# Joystick.net
KiCad netlist of a schematic drawn in EAGLE
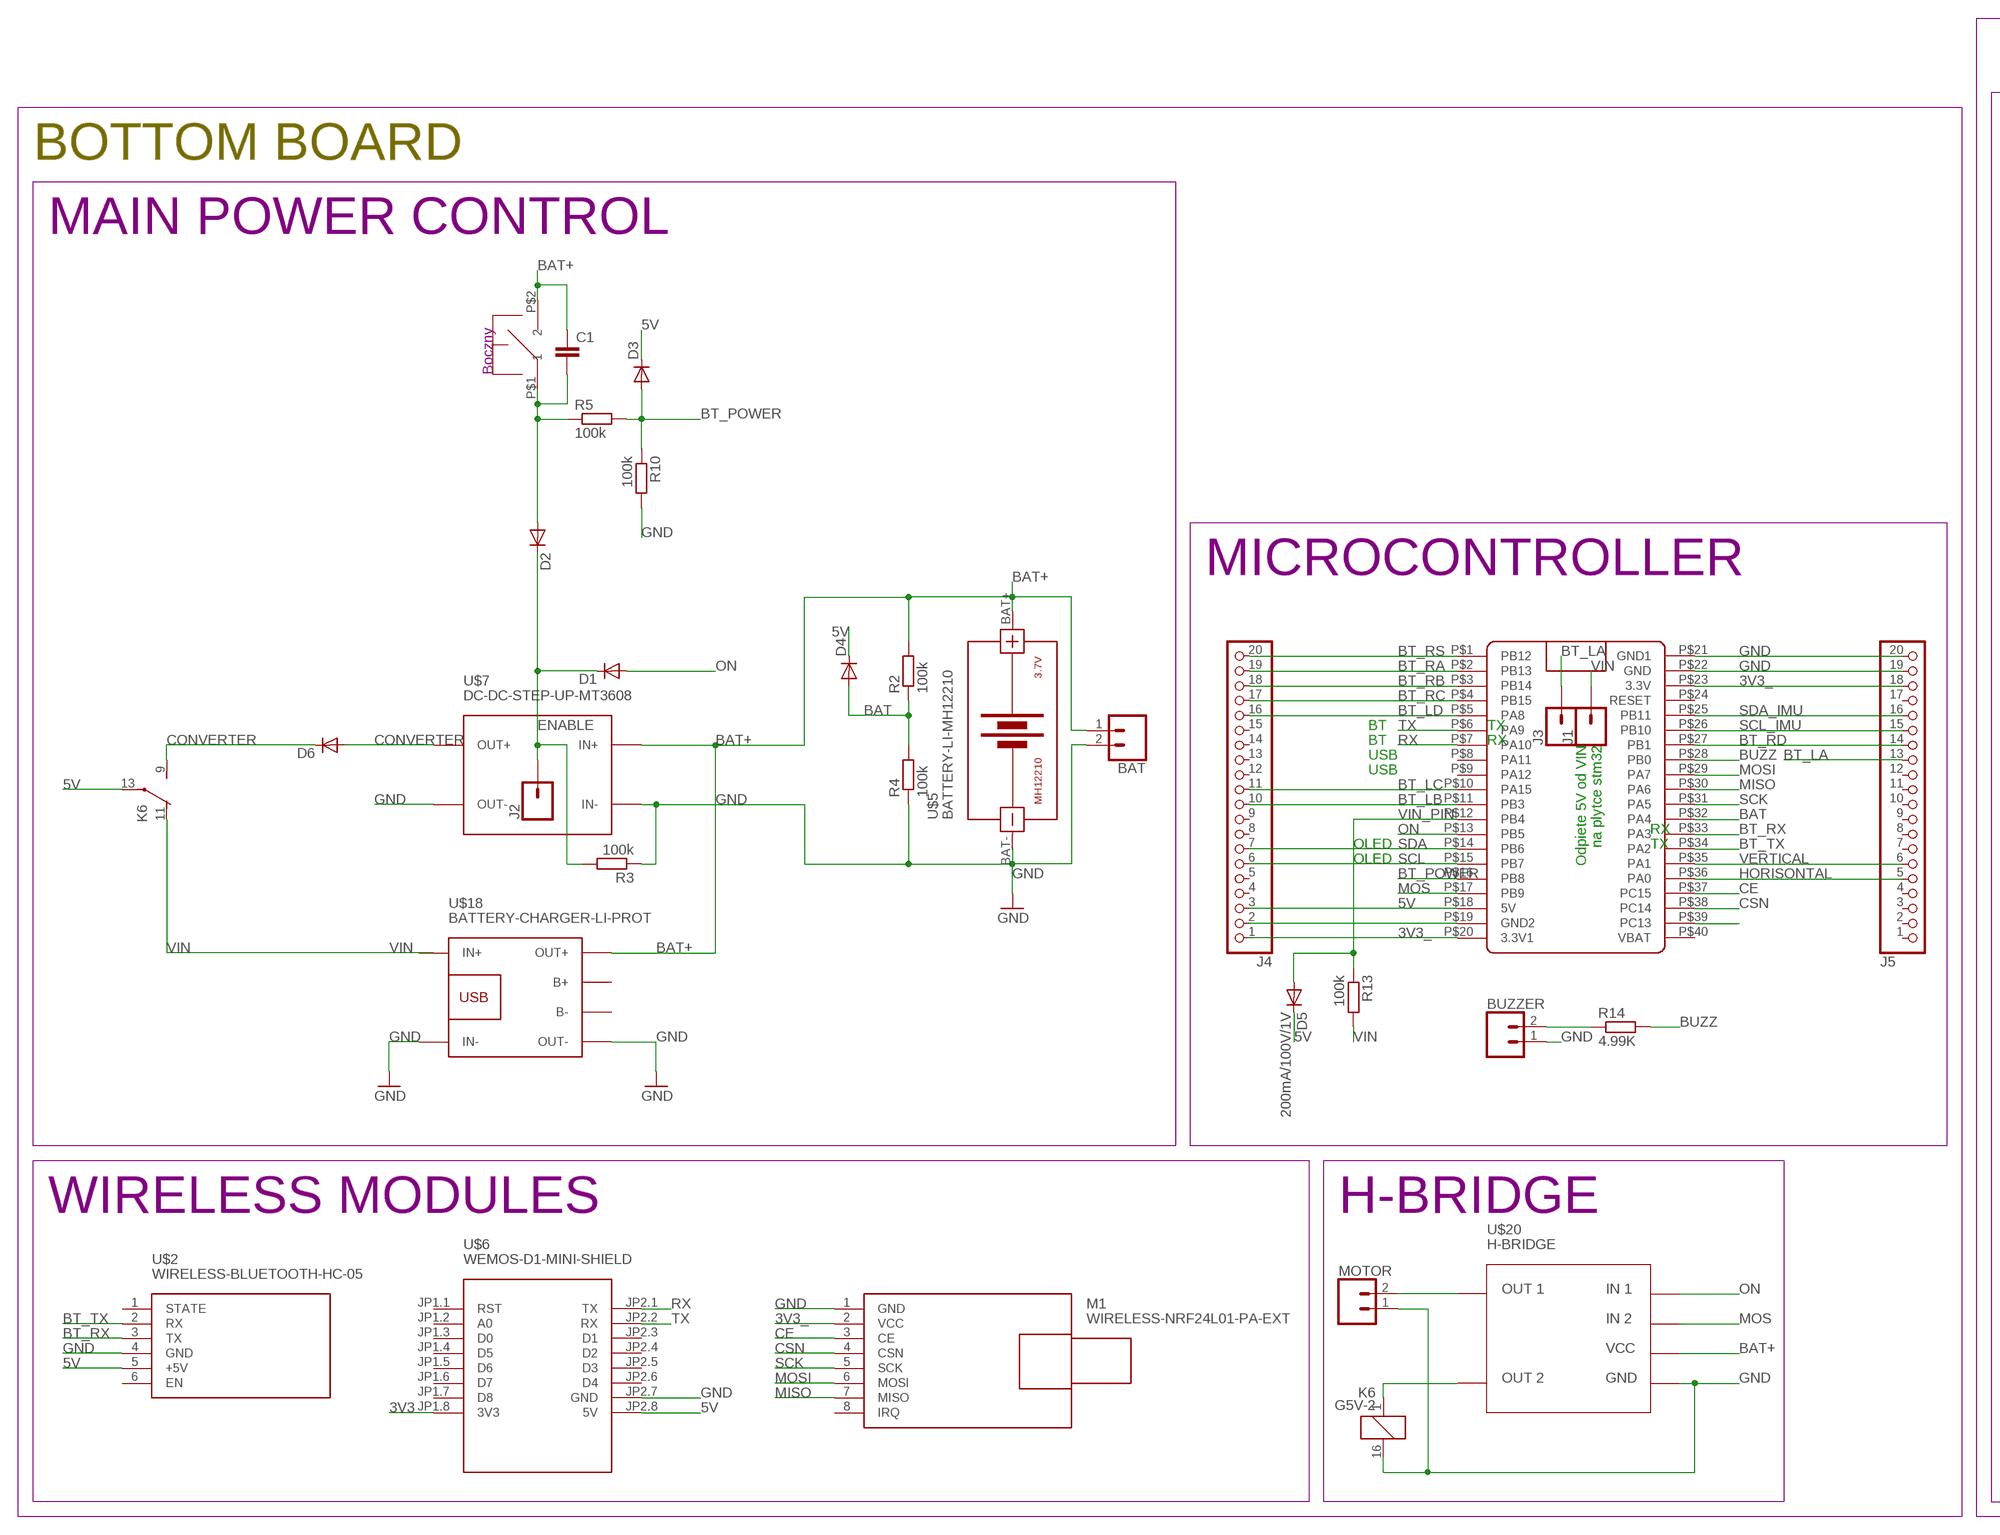
[diagram p0: schematic, sheet 1, part 1 of 2]
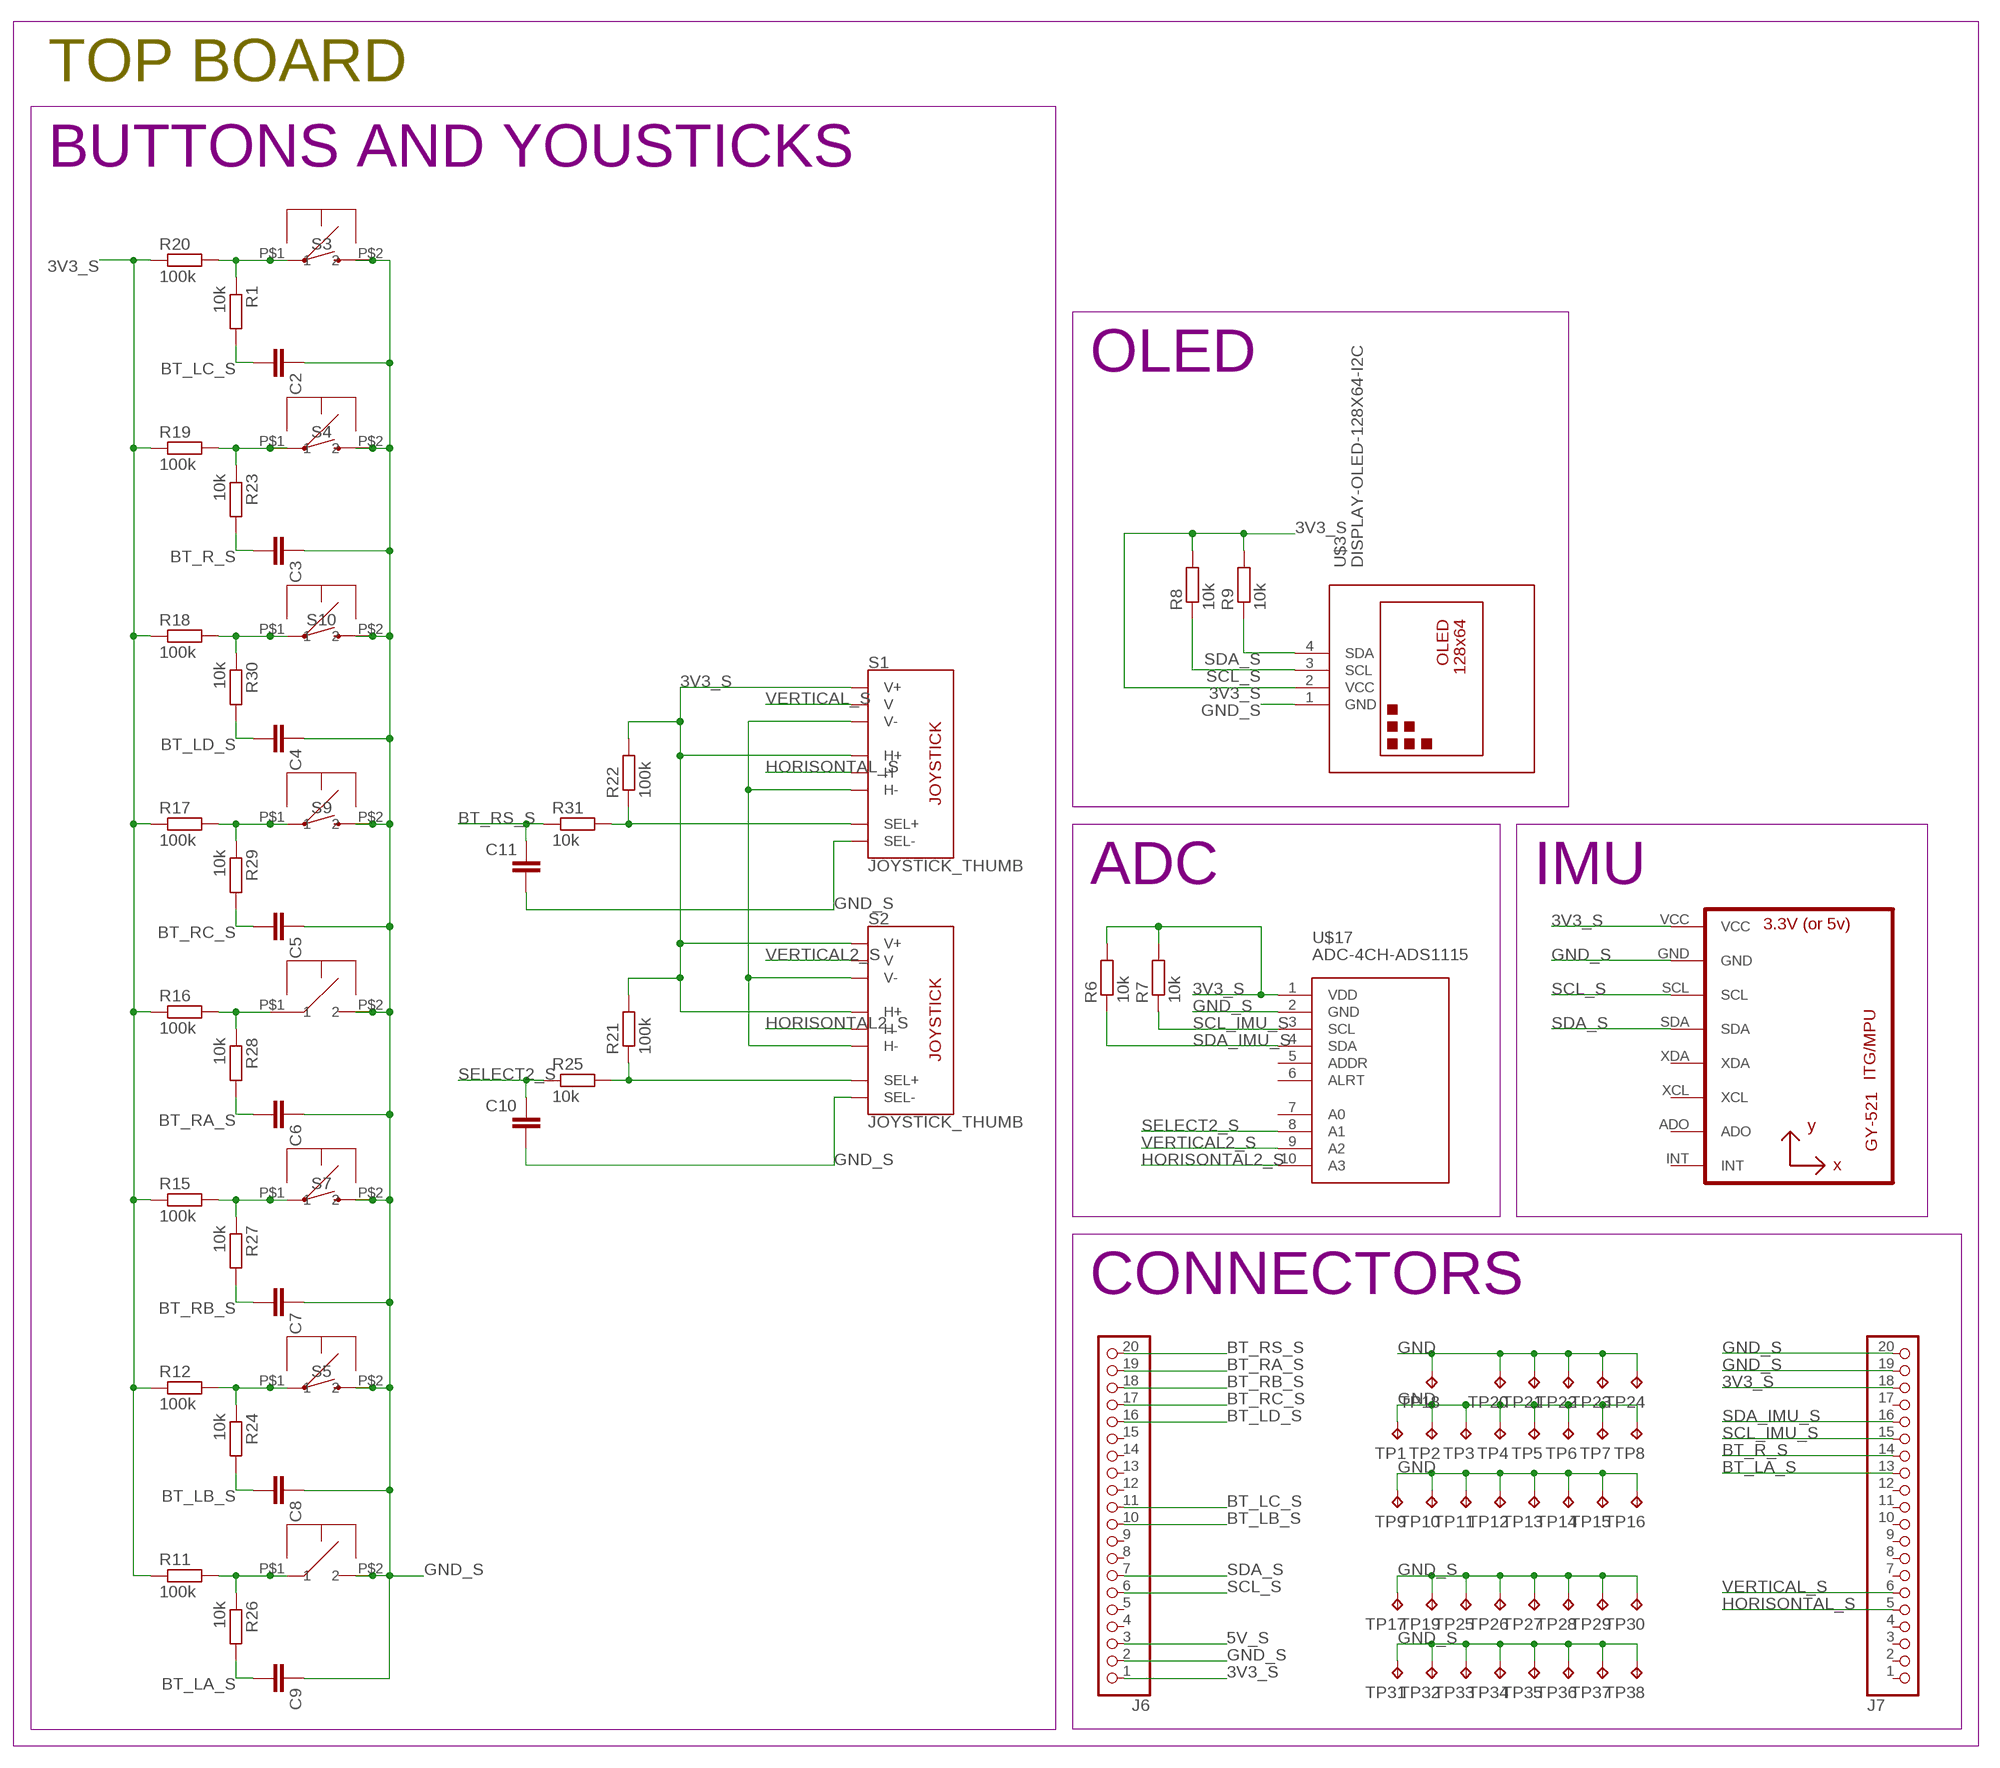
[diagram p1: schematic, sheet 1, part 2 of 2]

(export (version "E")
  (design (tool "Eeschema 10.0.6"))
  (components
    (comp (ref "BAT")
      (value "CONN_02")
      (footprint "eagle-import:1X02")
      (libsource (lib "eagle-import") (part "CONN_02"))
    )
    (comp (ref "BUZZER")
      (value "CONN_02")
      (footprint "eagle-import:1X02")
      (libsource (lib "eagle-import") (part "CONN_02"))
    )
    (comp (ref "C1")
      (value "C-EUC1206")
      (footprint "eagle-import:C1206")
      (libsource (lib "eagle-import") (part "C-EUC1206"))
    )
    (comp (ref "C2")
      (value "C-EUC1206")
      (footprint "eagle-import:C1206")
      (libsource (lib "eagle-import") (part "C-EUC1206"))
    )
    (comp (ref "C3")
      (value "C-EUC1206")
      (footprint "eagle-import:C1206")
      (libsource (lib "eagle-import") (part "C-EUC1206"))
    )
    (comp (ref "C4")
      (value "C-EUC1206")
      (footprint "eagle-import:C1206")
      (libsource (lib "eagle-import") (part "C-EUC1206"))
    )
    (comp (ref "C5")
      (value "C-EUC1206")
      (footprint "eagle-import:C1206")
      (libsource (lib "eagle-import") (part "C-EUC1206"))
    )
    (comp (ref "C6")
      (value "C-EUC1206")
      (footprint "eagle-import:C1206")
      (libsource (lib "eagle-import") (part "C-EUC1206"))
    )
    (comp (ref "C7")
      (value "C-EUC1206")
      (footprint "eagle-import:C1206")
      (libsource (lib "eagle-import") (part "C-EUC1206"))
    )
    (comp (ref "C8")
      (value "C-EUC1206")
      (footprint "eagle-import:C1206")
      (libsource (lib "eagle-import") (part "C-EUC1206"))
    )
    (comp (ref "C9")
      (value "C-EUC1206")
      (footprint "eagle-import:C1206")
      (libsource (lib "eagle-import") (part "C-EUC1206"))
    )
    (comp (ref "C10")
      (value "C-EUC1206")
      (footprint "eagle-import:C1206")
      (libsource (lib "eagle-import") (part "C-EUC1206"))
    )
    (comp (ref "C11")
      (value "C-EUC1206")
      (footprint "eagle-import:C1206")
      (libsource (lib "eagle-import") (part "C-EUC1206"))
    )
    (comp (ref "D1")
      (value "200mA/100V/1V")
      (footprint "eagle-import:DO214AC")
      (libsource (lib "eagle-import") (part "DIODE-DO214AC"))
    )
    (comp (ref "D2")
      (value "200mA/100V/1V")
      (footprint "eagle-import:DO214AC")
      (libsource (lib "eagle-import") (part "DIODE-DO214AC"))
    )
    (comp (ref "D3")
      (value "200mA/100V/1V")
      (footprint "eagle-import:DO214AC")
      (libsource (lib "eagle-import") (part "DIODE-DO214AC"))
    )
    (comp (ref "D4")
      (value "200mA/100V/1V")
      (footprint "eagle-import:DO214AC")
      (libsource (lib "eagle-import") (part "DIODE-DO214AC"))
    )
    (comp (ref "D5")
      (value "200mA/100V/1V")
      (footprint "eagle-import:DO214AC")
      (libsource (lib "eagle-import") (part "DIODE-DO214AC"))
    )
    (comp (ref "D6")
      (value "200mA/100V/1V")
      (footprint "eagle-import:DO214AC")
      (libsource (lib "eagle-import") (part "DIODE-DO214AC"))
    )
    (comp (ref "J1")
      (value "CONN_01")
      (footprint "eagle-import:1X01")
      (libsource (lib "eagle-import") (part "CONN_01"))
    )
    (comp (ref "J2")
      (value "CONN_01")
      (footprint "eagle-import:1X01")
      (libsource (lib "eagle-import") (part "CONN_01"))
    )
    (comp (ref "J3")
      (value "CONN_01")
      (footprint "eagle-import:1X01")
      (libsource (lib "eagle-import") (part "CONN_01"))
    )
    (comp (ref "J4")
      (value "PINHD-1X20")
      (footprint "eagle-import:1X20")
      (libsource (lib "eagle-import") (part "PINHD-1X20"))
    )
    (comp (ref "J5")
      (value "PINHD-1X20")
      (footprint "eagle-import:1X20")
      (libsource (lib "eagle-import") (part "PINHD-1X20"))
    )
    (comp (ref "J6")
      (value "PINHD-1X20")
      (footprint "eagle-import:1X20")
      (libsource (lib "eagle-import") (part "PINHD-1X20"))
    )
    (comp (ref "J7")
      (value "PINHD-1X20")
      (footprint "eagle-import:1X20")
      (libsource (lib "eagle-import") (part "PINHD-1X20"))
    )
    (comp (ref "K6")
      (value "G5V-2")
      (footprint "eagle-import:G5V-2")
      (fields (field (name "MPN") "G5V-2 5DC"))
      (libsource (lib "eagle-import") (part "G5V-2"))
    )
    (comp (ref "M1")
      (value "WIRELESS-NRF24L01-PA-EXT")
      (footprint "eagle-import:WIRELESS-NRF24L01-PA-EXT")
      (libsource (lib "eagle-import") (part "WIRELESS-NRF24L01-PA-EXT"))
    )
    (comp (ref "MOTOR")
      (value "CONN_02")
      (footprint "eagle-import:1X02")
      (libsource (lib "eagle-import") (part "CONN_02"))
    )
    (comp (ref "R1")
      (value "10k")
      (footprint "eagle-import:R0805")
      (libsource (lib "eagle-import") (part "R-EU_R0805"))
    )
    (comp (ref "R2")
      (value "100k")
      (footprint "eagle-import:R0805")
      (libsource (lib "eagle-import") (part "R-EU_R0805"))
    )
    (comp (ref "R3")
      (value "100k")
      (footprint "eagle-import:R0805")
      (libsource (lib "eagle-import") (part "R-EU_R0805"))
    )
    (comp (ref "R4")
      (value "100k")
      (footprint "eagle-import:R0805")
      (libsource (lib "eagle-import") (part "R-EU_R0805"))
    )
    (comp (ref "R5")
      (value "100k")
      (footprint "eagle-import:R0805")
      (libsource (lib "eagle-import") (part "R-EU_R0805"))
    )
    (comp (ref "R6")
      (value "10k")
      (footprint "eagle-import:R0805")
      (libsource (lib "eagle-import") (part "R-EU_R0805"))
    )
    (comp (ref "R7")
      (value "10k")
      (footprint "eagle-import:R0805")
      (libsource (lib "eagle-import") (part "R-EU_R0805"))
    )
    (comp (ref "R8")
      (value "10k")
      (footprint "eagle-import:R0805")
      (libsource (lib "eagle-import") (part "R-EU_R0805"))
    )
    (comp (ref "R9")
      (value "10k")
      (footprint "eagle-import:R0805")
      (libsource (lib "eagle-import") (part "R-EU_R0805"))
    )
    (comp (ref "R10")
      (value "100k")
      (footprint "eagle-import:R0805")
      (libsource (lib "eagle-import") (part "R-EU_R0805"))
    )
    (comp (ref "R11")
      (value "100k")
      (footprint "eagle-import:R0805")
      (libsource (lib "eagle-import") (part "R-EU_R0805"))
    )
    (comp (ref "R12")
      (value "100k")
      (footprint "eagle-import:R0805")
      (libsource (lib "eagle-import") (part "R-EU_R0805"))
    )
    (comp (ref "R13")
      (value "100k")
      (footprint "eagle-import:R0805")
      (libsource (lib "eagle-import") (part "R-EU_R0805"))
    )
    (comp (ref "R14")
      (value "4.99K")
      (footprint "eagle-import:R0805")
      (libsource (lib "eagle-import") (part "R-EU_R0805"))
    )
    (comp (ref "R15")
      (value "100k")
      (footprint "eagle-import:R0805")
      (libsource (lib "eagle-import") (part "R-EU_R0805"))
    )
    (comp (ref "R16")
      (value "100k")
      (footprint "eagle-import:R0805")
      (libsource (lib "eagle-import") (part "R-EU_R0805"))
    )
    (comp (ref "R17")
      (value "100k")
      (footprint "eagle-import:R0805")
      (libsource (lib "eagle-import") (part "R-EU_R0805"))
    )
    (comp (ref "R18")
      (value "100k")
      (footprint "eagle-import:R0805")
      (libsource (lib "eagle-import") (part "R-EU_R0805"))
    )
    (comp (ref "R19")
      (value "100k")
      (footprint "eagle-import:R0805")
      (libsource (lib "eagle-import") (part "R-EU_R0805"))
    )
    (comp (ref "R20")
      (value "100k")
      (footprint "eagle-import:R0805")
      (libsource (lib "eagle-import") (part "R-EU_R0805"))
    )
    (comp (ref "R21")
      (value "100k")
      (footprint "eagle-import:R0805")
      (libsource (lib "eagle-import") (part "R-EU_R0805"))
    )
    (comp (ref "R22")
      (value "100k")
      (footprint "eagle-import:R0805")
      (libsource (lib "eagle-import") (part "R-EU_R0805"))
    )
    (comp (ref "R23")
      (value "10k")
      (footprint "eagle-import:R0805")
      (libsource (lib "eagle-import") (part "R-EU_R0805"))
    )
    (comp (ref "R24")
      (value "10k")
      (footprint "eagle-import:R0805")
      (libsource (lib "eagle-import") (part "R-EU_R0805"))
    )
    (comp (ref "R25")
      (value "10k")
      (footprint "eagle-import:R0805")
      (libsource (lib "eagle-import") (part "R-EU_R0805"))
    )
    (comp (ref "R26")
      (value "10k")
      (footprint "eagle-import:R0805")
      (libsource (lib "eagle-import") (part "R-EU_R0805"))
    )
    (comp (ref "R27")
      (value "10k")
      (footprint "eagle-import:R0805")
      (libsource (lib "eagle-import") (part "R-EU_R0805"))
    )
    (comp (ref "R28")
      (value "10k")
      (footprint "eagle-import:R0805")
      (libsource (lib "eagle-import") (part "R-EU_R0805"))
    )
    (comp (ref "R29")
      (value "10k")
      (footprint "eagle-import:R0805")
      (libsource (lib "eagle-import") (part "R-EU_R0805"))
    )
    (comp (ref "R30")
      (value "10k")
      (footprint "eagle-import:R0805")
      (libsource (lib "eagle-import") (part "R-EU_R0805"))
    )
    (comp (ref "R31")
      (value "10k")
      (footprint "eagle-import:R0805")
      (libsource (lib "eagle-import") (part "R-EU_R0805"))
    )
    (comp (ref "S1")
      (value "JOYSTICK_THUMB")
      (footprint "eagle-import:JOYSTICK")
      (libsource (lib "eagle-import") (part "JOYSTICK_THUMB"))
    )
    (comp (ref "S2")
      (value "JOYSTICK_THUMB")
      (footprint "eagle-import:JOYSTICK")
      (libsource (lib "eagle-import") (part "JOYSTICK_THUMB"))
    )
    (comp (ref "S3")
      (value "MOMENTARY-SWITCH-SPST-PTH-12MM")
      (footprint "eagle-import:TACTILE_SWITCH_PTH_12MM")
      (libsource (lib "eagle-import") (part "MOMENTARY-SWITCH-SPST-PTH-12MM"))
    )
    (comp (ref "S4")
      (value "MOMENTARY-SWITCH-SPST-PTH-12MM")
      (footprint "eagle-import:TACTILE_SWITCH_PTH_12MM")
      (libsource (lib "eagle-import") (part "MOMENTARY-SWITCH-SPST-PTH-12MM"))
    )
    (comp (ref "S5")
      (value "MOMENTARY-SWITCH-SPST-PTH-12MM")
      (footprint "eagle-import:TACTILE_SWITCH_PTH_12MM")
      (libsource (lib "eagle-import") (part "MOMENTARY-SWITCH-SPST-PTH-12MM"))
    )
    (comp (ref "S7")
      (value "MOMENTARY-SWITCH-SPST-PTH-12MM")
      (footprint "eagle-import:TACTILE_SWITCH_PTH_12MM")
      (libsource (lib "eagle-import") (part "MOMENTARY-SWITCH-SPST-PTH-12MM"))
    )
    (comp (ref "S9")
      (value "MOMENTARY-SWITCH-SPST-PTH-12MM")
      (footprint "eagle-import:TACTILE_SWITCH_PTH_12MM")
      (libsource (lib "eagle-import") (part "MOMENTARY-SWITCH-SPST-PTH-12MM"))
    )
    (comp (ref "S10")
      (value "MOMENTARY-SWITCH-SPST-PTH-12MM")
      (footprint "eagle-import:TACTILE_SWITCH_PTH_12MM")
      (libsource (lib "eagle-import") (part "MOMENTARY-SWITCH-SPST-PTH-12MM"))
    )
    (comp (ref "TP1")
      (value "TPB1,27")
      (footprint "eagle-import:B1,27")
      (libsource (lib "eagle-import") (part "TPB1,27"))
    )
    (comp (ref "TP2")
      (value "TPB1,27")
      (footprint "eagle-import:B1,27")
      (libsource (lib "eagle-import") (part "TPB1,27"))
    )
    (comp (ref "TP3")
      (value "TPB1,27")
      (footprint "eagle-import:B1,27")
      (libsource (lib "eagle-import") (part "TPB1,27"))
    )
    (comp (ref "TP4")
      (value "TPB1,27")
      (footprint "eagle-import:B1,27")
      (libsource (lib "eagle-import") (part "TPB1,27"))
    )
    (comp (ref "TP5")
      (value "TPB1,27")
      (footprint "eagle-import:B1,27")
      (libsource (lib "eagle-import") (part "TPB1,27"))
    )
    (comp (ref "TP6")
      (value "TPB1,27")
      (footprint "eagle-import:B1,27")
      (libsource (lib "eagle-import") (part "TPB1,27"))
    )
    (comp (ref "TP7")
      (value "TPB1,27")
      (footprint "eagle-import:B1,27")
      (libsource (lib "eagle-import") (part "TPB1,27"))
    )
    (comp (ref "TP8")
      (value "TPB1,27")
      (footprint "eagle-import:B1,27")
      (libsource (lib "eagle-import") (part "TPB1,27"))
    )
    (comp (ref "TP9")
      (value "TPB1,27")
      (footprint "eagle-import:B1,27")
      (libsource (lib "eagle-import") (part "TPB1,27"))
    )
    (comp (ref "TP10")
      (value "TPB1,27")
      (footprint "eagle-import:B1,27")
      (libsource (lib "eagle-import") (part "TPB1,27"))
    )
    (comp (ref "TP11")
      (value "TPB1,27")
      (footprint "eagle-import:B1,27")
      (libsource (lib "eagle-import") (part "TPB1,27"))
    )
    (comp (ref "TP12")
      (value "TPB1,27")
      (footprint "eagle-import:B1,27")
      (libsource (lib "eagle-import") (part "TPB1,27"))
    )
    (comp (ref "TP13")
      (value "TPB1,27")
      (footprint "eagle-import:B1,27")
      (libsource (lib "eagle-import") (part "TPB1,27"))
    )
    (comp (ref "TP14")
      (value "TPB1,27")
      (footprint "eagle-import:B1,27")
      (libsource (lib "eagle-import") (part "TPB1,27"))
    )
    (comp (ref "TP15")
      (value "TPB1,27")
      (footprint "eagle-import:B1,27")
      (libsource (lib "eagle-import") (part "TPB1,27"))
    )
    (comp (ref "TP16")
      (value "TPB1,27")
      (footprint "eagle-import:B1,27")
      (libsource (lib "eagle-import") (part "TPB1,27"))
    )
    (comp (ref "TP17")
      (value "TPB1,27")
      (footprint "eagle-import:B1,27")
      (libsource (lib "eagle-import") (part "TPB1,27"))
    )
    (comp (ref "TP18")
      (value "TPB1,27")
      (footprint "eagle-import:B1,27")
      (libsource (lib "eagle-import") (part "TPB1,27"))
    )
    (comp (ref "TP19")
      (value "TPB1,27")
      (footprint "eagle-import:B1,27")
      (libsource (lib "eagle-import") (part "TPB1,27"))
    )
    (comp (ref "TP20")
      (value "TPB1,27")
      (footprint "eagle-import:B1,27")
      (libsource (lib "eagle-import") (part "TPB1,27"))
    )
    (comp (ref "TP21")
      (value "TPB1,27")
      (footprint "eagle-import:B1,27")
      (libsource (lib "eagle-import") (part "TPB1,27"))
    )
    (comp (ref "TP22")
      (value "TPB1,27")
      (footprint "eagle-import:B1,27")
      (libsource (lib "eagle-import") (part "TPB1,27"))
    )
    (comp (ref "TP23")
      (value "TPB1,27")
      (footprint "eagle-import:B1,27")
      (libsource (lib "eagle-import") (part "TPB1,27"))
    )
    (comp (ref "TP24")
      (value "TPB1,27")
      (footprint "eagle-import:B1,27")
      (libsource (lib "eagle-import") (part "TPB1,27"))
    )
    (comp (ref "TP25")
      (value "TPB1,27")
      (footprint "eagle-import:B1,27")
      (libsource (lib "eagle-import") (part "TPB1,27"))
    )
    (comp (ref "TP26")
      (value "TPB1,27")
      (footprint "eagle-import:B1,27")
      (libsource (lib "eagle-import") (part "TPB1,27"))
    )
    (comp (ref "TP27")
      (value "TPB1,27")
      (footprint "eagle-import:B1,27")
      (libsource (lib "eagle-import") (part "TPB1,27"))
    )
    (comp (ref "TP28")
      (value "TPB1,27")
      (footprint "eagle-import:B1,27")
      (libsource (lib "eagle-import") (part "TPB1,27"))
    )
    (comp (ref "TP29")
      (value "TPB1,27")
      (footprint "eagle-import:B1,27")
      (libsource (lib "eagle-import") (part "TPB1,27"))
    )
    (comp (ref "TP30")
      (value "TPB1,27")
      (footprint "eagle-import:B1,27")
      (libsource (lib "eagle-import") (part "TPB1,27"))
    )
    (comp (ref "TP31")
      (value "TPB1,27")
      (footprint "eagle-import:B1,27")
      (libsource (lib "eagle-import") (part "TPB1,27"))
    )
    (comp (ref "TP32")
      (value "TPB1,27")
      (footprint "eagle-import:B1,27")
      (libsource (lib "eagle-import") (part "TPB1,27"))
    )
    (comp (ref "TP33")
      (value "TPB1,27")
      (footprint "eagle-import:B1,27")
      (libsource (lib "eagle-import") (part "TPB1,27"))
    )
    (comp (ref "TP34")
      (value "TPB1,27")
      (footprint "eagle-import:B1,27")
      (libsource (lib "eagle-import") (part "TPB1,27"))
    )
    (comp (ref "TP35")
      (value "TPB1,27")
      (footprint "eagle-import:B1,27")
      (libsource (lib "eagle-import") (part "TPB1,27"))
    )
    (comp (ref "TP36")
      (value "TPB1,27")
      (footprint "eagle-import:B1,27")
      (libsource (lib "eagle-import") (part "TPB1,27"))
    )
    (comp (ref "TP37")
      (value "TPB1,27")
      (footprint "eagle-import:B1,27")
      (libsource (lib "eagle-import") (part "TPB1,27"))
    )
    (comp (ref "TP38")
      (value "TPB1,27")
      (footprint "eagle-import:B1,27")
      (libsource (lib "eagle-import") (part "TPB1,27"))
    )
    (comp (ref "U$1")
      (value "BLUE_PILL")
      (footprint "eagle-import:BLUE_PILL")
      (libsource (lib "eagle-import") (part "BLUE_PILL"))
    )
    (comp (ref "U$2")
      (value "WIRELESS-BLUETOOTH-HC-05")
      (footprint "eagle-import:WIRELESS-BLUETOOTH-HC-05")
      (libsource (lib "eagle-import") (part "WIRELESS-BLUETOOTH-HC-05"))
    )
    (comp (ref "U$3")
      (value "DISPLAY-OLED-128X64-I2C")
      (footprint "eagle-import:DISPLAY-OLED-128X64-I2C")
      (libsource (lib "eagle-import") (part "DISPLAY-OLED-128X64-I2C"))
    )
    (comp (ref "U$4")
      (value "MOUSE_BT")
      (footprint "eagle-import:MOUSE_BT")
      (libsource (lib "eagle-import") (part "MOUSE_BT"))
    )
    (comp (ref "U$5")
      (value "BATTERY-LI-MH12210")
      (footprint "eagle-import:BATTERY-LI-MH12210")
      (libsource (lib "eagle-import") (part "BATTERY-LI-MH12210"))
    )
    (comp (ref "U$6")
      (value "WEMOS-D1-MINI-SHIELD")
      (footprint "eagle-import:WEMOS-D1-MINI-SHIELD")
      (libsource (lib "eagle-import") (part "WEMOS-D1-MINI-SHIELD"))
    )
    (comp (ref "U$7")
      (value "DC-DC-STEP-UP-MT3608")
      (footprint "eagle-import:DC-DC-STEP-UP-MT3608")
      (libsource (lib "eagle-import") (part "DC-DC-STEP-UP-MT3608"))
    )
    (comp (ref "U$8")
      (value "MOUSE_BT")
      (footprint "eagle-import:MOUSE_BT")
      (libsource (lib "eagle-import") (part "MOUSE_BT"))
    )
    (comp (ref "U$9")
      (value "MOUSE_BT")
      (footprint "eagle-import:MOUSE_BT")
      (libsource (lib "eagle-import") (part "MOUSE_BT"))
    )
    (comp (ref "U$10")
      (value "MOUSE_BT")
      (footprint "eagle-import:MOUSE_BT")
      (libsource (lib "eagle-import") (part "MOUSE_BT"))
    )
    (comp (ref "U$11")
      (value "MOUSE_BT")
      (footprint "eagle-import:MOUSE_BT")
      (libsource (lib "eagle-import") (part "MOUSE_BT"))
    )
    (comp (ref "U$12")
      (value "MOUSE_BT")
      (footprint "eagle-import:MOUSE_BT")
      (libsource (lib "eagle-import") (part "MOUSE_BT"))
    )
    (comp (ref "U$13")
      (value "MOUSE_BT")
      (footprint "eagle-import:MOUSE_BT")
      (libsource (lib "eagle-import") (part "MOUSE_BT"))
    )
    (comp (ref "U$14")
      (value "MOUSE_BT")
      (footprint "eagle-import:MOUSE_BT")
      (libsource (lib "eagle-import") (part "MOUSE_BT"))
    )
    (comp (ref "U$16")
      (value "MOUSE_BT")
      (footprint "eagle-import:MOUSE_BT")
      (libsource (lib "eagle-import") (part "MOUSE_BT"))
    )
    (comp (ref "U$17")
      (value "ADC-4CH-ADS1115")
      (footprint "eagle-import:ADC-4CH-ADS1115")
      (libsource (lib "eagle-import") (part "ADC-4CH-ADS1115"))
    )
    (comp (ref "U$18")
      (value "BATTERY-CHARGER-LI-PROT")
      (footprint "eagle-import:BATTERY-CHARGER-LI-PROT")
      (libsource (lib "eagle-import") (part "BATTERY-CHARGER-LI-PROT"))
    )
    (comp (ref "U1")
      (value "GY-521MPU6050")
      (footprint "eagle-import:GY-521")
      (libsource (lib "eagle-import") (part "GY-521MPU6050"))
    )
  )
  (nets
    (net (code "1") (name "/3V3") (class "Default")
      (node (ref "U$6") (pin "JP1.8") (pinfunction "3V3_JP1.8") (pintype "power_in"))
    )
    (net (code "2") (name "/3V3_") (class "Default")
      (node (ref "J4") (pin "1") (pinfunction "1_1") (pintype "passive"))
      (node (ref "J5") (pin "18") (pinfunction "18_18") (pintype "passive"))
      (node (ref "M1") (pin "2") (pinfunction "VCC_2") (pintype "power_in"))
      (node (ref "U$1") (pin "P$20") (pinfunction "3.3V1_P$20") (pintype "bidirectional"))
      (node (ref "U$1") (pin "P$23") (pinfunction "3.3V_P$23") (pintype "bidirectional"))
    )
    (net (code "3") (name "/3V3_S") (class "Default")
      (node (ref "J6") (pin "1") (pinfunction "1_1") (pintype "passive"))
      (node (ref "J7") (pin "18") (pinfunction "18_18") (pintype "passive"))
      (node (ref "R11") (pin "1") (pinfunction "1_1") (pintype "passive"))
      (node (ref "R12") (pin "1") (pinfunction "1_1") (pintype "passive"))
      (node (ref "R15") (pin "1") (pinfunction "1_1") (pintype "passive"))
      (node (ref "R16") (pin "1") (pinfunction "1_1") (pintype "passive"))
      (node (ref "R17") (pin "1") (pinfunction "1_1") (pintype "passive"))
      (node (ref "R18") (pin "1") (pinfunction "1_1") (pintype "passive"))
      (node (ref "R19") (pin "1") (pinfunction "1_1") (pintype "passive"))
      (node (ref "R20") (pin "1") (pinfunction "1_1") (pintype "passive"))
      (node (ref "R21") (pin "2") (pinfunction "2_2") (pintype "passive"))
      (node (ref "R22") (pin "2") (pinfunction "2_2") (pintype "passive"))
      (node (ref "R6") (pin "2") (pinfunction "2_2") (pintype "passive"))
      (node (ref "R7") (pin "2") (pinfunction "2_2") (pintype "passive"))
      (node (ref "R8") (pin "2") (pinfunction "2_2") (pintype "passive"))
      (node (ref "R9") (pin "2") (pinfunction "2_2") (pintype "passive"))
      (node (ref "S1") (pin "H1") (pinfunction "H+_H1") (pintype "bidirectional"))
      (node (ref "S1") (pin "V1") (pinfunction "V+_V1") (pintype "bidirectional"))
      (node (ref "S2") (pin "H1") (pinfunction "H+_H1") (pintype "bidirectional"))
      (node (ref "S2") (pin "V1") (pinfunction "V+_V1") (pintype "bidirectional"))
      (node (ref "U$17") (pin "1") (pinfunction "VDD_1") (pintype "power_in"))
      (node (ref "U$3") (pin "2") (pinfunction "VCC_2") (pintype "power_in"))
      (node (ref "U1") (pin "VCC") (pinfunction "VCC_VCC") (pintype "bidirectional"))
    )
    (net (code "4") (name "/5V") (class "Default")
      (node (ref "D3") (pin "C") (pinfunction "C_C") (pintype "passive"))
      (node (ref "D4") (pin "C") (pinfunction "C_C") (pintype "passive"))
      (node (ref "D5") (pin "C") (pinfunction "C_C") (pintype "passive"))
      (node (ref "J4") (pin "3") (pinfunction "3_3") (pintype "passive"))
      (node (ref "K6") (pin "13") (pinfunction "P_13") (pintype "passive"))
      (node (ref "U$1") (pin "P$18") (pinfunction "5V_P$18") (pintype "bidirectional"))
      (node (ref "U$2") (pin "5") (pinfunction "+5V_5") (pintype "power_in"))
      (node (ref "U$6") (pin "JP2.8") (pinfunction "5V_JP2.8") (pintype "power_in"))
    )
    (net (code "5") (name "/5V_S") (class "Default")
      (node (ref "J6") (pin "3") (pinfunction "3_3") (pintype "passive"))
    )
    (net (code "6") (name "/BAT") (class "Default")
      (node (ref "D4") (pin "A") (pinfunction "A_A") (pintype "passive"))
      (node (ref "R2") (pin "1") (pinfunction "1_1") (pintype "passive"))
      (node (ref "R4") (pin "2") (pinfunction "2_2") (pintype "passive"))
      (node (ref "U$1") (pin "P$32") (pinfunction "PA4_P$32") (pintype "bidirectional"))
    )
    (net (code "7") (name "/BAT+") (class "Default")
      (node (ref "BAT") (pin "1") (pinfunction "1_1") (pintype "passive"))
      (node (ref "C1") (pin "1") (pinfunction "1_1") (pintype "passive"))
      (node (ref "R2") (pin "2") (pinfunction "2_2") (pintype "passive"))
      (node (ref "U$18") (pin "OUT+") (pinfunction "OUT+_OUT+") (pintype "bidirectional"))
      (node (ref "U$5") (pin "BAT+") (pinfunction "BAT+_BAT+") (pintype "power_in"))
      (node (ref "U$7") (pin "IN+") (pinfunction "IN+_IN+") (pintype "bidirectional"))
      (node (ref "U$8") (pin "P$2") (pinfunction "2_P$2") (pintype "bidirectional"))
    )
    (net (code "8") (name "/BT_LA") (class "Default")
      (node (ref "J3") (pin "1") (pinfunction "1_1") (pintype "passive"))
      (node (ref "J5") (pin "13") (pinfunction "13_13") (pintype "passive"))
    )
    (net (code "9") (name "/BT_LA_S") (class "Default")
      (node (ref "C9") (pin "2") (pinfunction "2_2") (pintype "passive"))
      (node (ref "J7") (pin "13") (pinfunction "13_13") (pintype "passive"))
      (node (ref "R26") (pin "2") (pinfunction "2_2") (pintype "passive"))
    )
    (net (code "10") (name "/BT_LB") (class "Default")
      (node (ref "J4") (pin "10") (pinfunction "10_10") (pintype "passive"))
      (node (ref "U$1") (pin "P$11") (pinfunction "PB3_P$11") (pintype "bidirectional"))
    )
    (net (code "11") (name "/BT_LB_S") (class "Default")
      (node (ref "C8") (pin "2") (pinfunction "2_2") (pintype "passive"))
      (node (ref "J6") (pin "10") (pinfunction "10_10") (pintype "passive"))
      (node (ref "R24") (pin "2") (pinfunction "2_2") (pintype "passive"))
    )
    (net (code "12") (name "/BT_LC") (class "Default")
      (node (ref "J4") (pin "11") (pinfunction "11_11") (pintype "passive"))
      (node (ref "U$1") (pin "P$10") (pinfunction "PA15_P$10") (pintype "bidirectional"))
    )
    (net (code "13") (name "/BT_LC_S") (class "Default")
      (node (ref "C2") (pin "2") (pinfunction "2_2") (pintype "passive"))
      (node (ref "J6") (pin "11") (pinfunction "11_11") (pintype "passive"))
      (node (ref "R1") (pin "2") (pinfunction "2_2") (pintype "passive"))
    )
    (net (code "14") (name "/BT_LD") (class "Default")
      (node (ref "J4") (pin "16") (pinfunction "16_16") (pintype "passive"))
      (node (ref "U$1") (pin "P$5") (pinfunction "PA8_P$5") (pintype "bidirectional"))
    )
    (net (code "15") (name "/BT_LD_S") (class "Default")
      (node (ref "C4") (pin "2") (pinfunction "2_2") (pintype "passive"))
      (node (ref "J6") (pin "16") (pinfunction "16_16") (pintype "passive"))
      (node (ref "R30") (pin "2") (pinfunction "2_2") (pintype "passive"))
    )
    (net (code "16") (name "/BT_POWER") (class "Default")
      (node (ref "D3") (pin "A") (pinfunction "A_A") (pintype "passive"))
      (node (ref "R10") (pin "1") (pinfunction "1_1") (pintype "passive"))
      (node (ref "R5") (pin "2") (pinfunction "2_2") (pintype "passive"))
      (node (ref "U$1") (pin "P$16") (pinfunction "PB8_P$16") (pintype "bidirectional"))
    )
    (net (code "17") (name "/BT_RA") (class "Default")
      (node (ref "J4") (pin "19") (pinfunction "19_19") (pintype "passive"))
      (node (ref "U$1") (pin "P$2") (pinfunction "PB13_P$2") (pintype "bidirectional"))
    )
    (net (code "18") (name "/BT_RA_S") (class "Default")
      (node (ref "C6") (pin "2") (pinfunction "2_2") (pintype "passive"))
      (node (ref "J6") (pin "19") (pinfunction "19_19") (pintype "passive"))
      (node (ref "R28") (pin "2") (pinfunction "2_2") (pintype "passive"))
    )
    (net (code "19") (name "/BT_RB") (class "Default")
      (node (ref "J4") (pin "18") (pinfunction "18_18") (pintype "passive"))
      (node (ref "U$1") (pin "P$3") (pinfunction "PB14_P$3") (pintype "bidirectional"))
    )
    (net (code "20") (name "/BT_RB_S") (class "Default")
      (node (ref "C7") (pin "2") (pinfunction "2_2") (pintype "passive"))
      (node (ref "J6") (pin "18") (pinfunction "18_18") (pintype "passive"))
      (node (ref "R27") (pin "2") (pinfunction "2_2") (pintype "passive"))
    )
    (net (code "21") (name "/BT_RC") (class "Default")
      (node (ref "J4") (pin "17") (pinfunction "17_17") (pintype "passive"))
      (node (ref "U$1") (pin "P$4") (pinfunction "PB15_P$4") (pintype "bidirectional"))
    )
    (net (code "22") (name "/BT_RC_S") (class "Default")
      (node (ref "C5") (pin "2") (pinfunction "2_2") (pintype "passive"))
      (node (ref "J6") (pin "17") (pinfunction "17_17") (pintype "passive"))
      (node (ref "R29") (pin "2") (pinfunction "2_2") (pintype "passive"))
    )
    (net (code "23") (name "/BT_RD") (class "Default")
      (node (ref "J5") (pin "14") (pinfunction "14_14") (pintype "passive"))
      (node (ref "U$1") (pin "P$27") (pinfunction "PB1_P$27") (pintype "bidirectional"))
    )
    (net (code "24") (name "/BT_RS") (class "Default")
      (node (ref "J4") (pin "20") (pinfunction "20_20") (pintype "passive"))
      (node (ref "U$1") (pin "P$1") (pinfunction "PB12_P$1") (pintype "bidirectional"))
    )
    (net (code "25") (name "/BT_RS_S") (class "Default")
      (node (ref "C11") (pin "1") (pinfunction "1_1") (pintype "passive"))
      (node (ref "J6") (pin "20") (pinfunction "20_20") (pintype "passive"))
      (node (ref "R31") (pin "1") (pinfunction "1_1") (pintype "passive"))
    )
    (net (code "26") (name "/BT_RX") (class "Default")
      (node (ref "U$1") (pin "P$33") (pinfunction "PA3_P$33") (pintype "bidirectional"))
      (node (ref "U$2") (pin "3") (pinfunction "TX_3") (pintype "bidirectional"))
    )
    (net (code "27") (name "/BT_R_S") (class "Default")
      (node (ref "C3") (pin "2") (pinfunction "2_2") (pintype "passive"))
      (node (ref "J7") (pin "14") (pinfunction "14_14") (pintype "passive"))
      (node (ref "R23") (pin "2") (pinfunction "2_2") (pintype "passive"))
    )
    (net (code "28") (name "/BT_TX") (class "Default")
      (node (ref "U$1") (pin "P$34") (pinfunction "PA2_P$34") (pintype "bidirectional"))
      (node (ref "U$2") (pin "2") (pinfunction "RX_2") (pintype "bidirectional"))
    )
    (net (code "29") (name "/BUZZ") (class "Default")
      (node (ref "R14") (pin "2") (pinfunction "2_2") (pintype "passive"))
      (node (ref "U$1") (pin "P$28") (pinfunction "PB0_P$28") (pintype "bidirectional"))
    )
    (net (code "30") (name "/CE") (class "Default")
      (node (ref "M1") (pin "3") (pinfunction "CE_3") (pintype "bidirectional"))
      (node (ref "U$1") (pin "P$37") (pinfunction "PC15_P$37") (pintype "bidirectional"))
    )
    (net (code "31") (name "/CONVERTER") (class "Default")
      (node (ref "D6") (pin "C") (pinfunction "C_C") (pintype "passive"))
      (node (ref "K6") (pin "9") (pinfunction "S_9") (pintype "passive"))
    )
    (net (code "32") (name "/CSN") (class "Default")
      (node (ref "M1") (pin "4") (pinfunction "CSN_4") (pintype "bidirectional"))
      (node (ref "U$1") (pin "P$38") (pinfunction "PC14_P$38") (pintype "bidirectional"))
    )
    (net (code "33") (name "/ENABLE") (class "Default")
      (node (ref "D1") (pin "C") (pinfunction "C_C") (pintype "passive"))
      (node (ref "D2") (pin "C") (pinfunction "C_C") (pintype "passive"))
      (node (ref "J2") (pin "1") (pinfunction "1_1") (pintype "passive"))
      (node (ref "R3") (pin "2") (pinfunction "2_2") (pintype "passive"))
    )
    (net (code "34") (name "/GND_S") (class "Default")
      (node (ref "C10") (pin "2") (pinfunction "2_2") (pintype "passive"))
      (node (ref "C11") (pin "2") (pinfunction "2_2") (pintype "passive"))
      (node (ref "C2") (pin "1") (pinfunction "1_1") (pintype "passive"))
      (node (ref "C3") (pin "1") (pinfunction "1_1") (pintype "passive"))
      (node (ref "C4") (pin "1") (pinfunction "1_1") (pintype "passive"))
      (node (ref "C5") (pin "1") (pinfunction "1_1") (pintype "passive"))
      (node (ref "C6") (pin "1") (pinfunction "1_1") (pintype "passive"))
      (node (ref "C7") (pin "1") (pinfunction "1_1") (pintype "passive"))
      (node (ref "C8") (pin "1") (pinfunction "1_1") (pintype "passive"))
      (node (ref "C9") (pin "1") (pinfunction "1_1") (pintype "passive"))
      (node (ref "J6") (pin "2") (pinfunction "2_2") (pintype "passive"))
      (node (ref "J7") (pin "19") (pinfunction "19_19") (pintype "passive"))
      (node (ref "J7") (pin "20") (pinfunction "20_20") (pintype "passive"))
      (node (ref "S1") (pin "B2A") (pinfunction "SEL-_B2A") (pintype "bidirectional"))
      (node (ref "S1") (pin "H3") (pinfunction "H-_H3") (pintype "bidirectional"))
      (node (ref "S1") (pin "V3") (pinfunction "V-_V3") (pintype "bidirectional"))
      (node (ref "S10") (pin "3") (pinfunction "2_3") (pintype "passive"))
      (node (ref "S2") (pin "B2A") (pinfunction "SEL-_B2A") (pintype "bidirectional"))
      (node (ref "S2") (pin "H3") (pinfunction "H-_H3") (pintype "bidirectional"))
      (node (ref "S2") (pin "V3") (pinfunction "V-_V3") (pintype "bidirectional"))
      (node (ref "S3") (pin "3") (pinfunction "2_3") (pintype "passive"))
      (node (ref "S4") (pin "3") (pinfunction "2_3") (pintype "passive"))
      (node (ref "S5") (pin "3") (pinfunction "2_3") (pintype "passive"))
      (node (ref "S7") (pin "3") (pinfunction "2_3") (pintype "passive"))
      (node (ref "S9") (pin "3") (pinfunction "2_3") (pintype "passive"))
      (node (ref "TP17") (pin "TP") (pinfunction "TP_TP") (pintype "input"))
      (node (ref "TP19") (pin "TP") (pinfunction "TP_TP") (pintype "input"))
      (node (ref "TP25") (pin "TP") (pinfunction "TP_TP") (pintype "input"))
      (node (ref "TP26") (pin "TP") (pinfunction "TP_TP") (pintype "input"))
      (node (ref "TP27") (pin "TP") (pinfunction "TP_TP") (pintype "input"))
      (node (ref "TP28") (pin "TP") (pinfunction "TP_TP") (pintype "input"))
      (node (ref "TP29") (pin "TP") (pinfunction "TP_TP") (pintype "input"))
      (node (ref "TP30") (pin "TP") (pinfunction "TP_TP") (pintype "input"))
      (node (ref "TP31") (pin "TP") (pinfunction "TP_TP") (pintype "input"))
      (node (ref "TP32") (pin "TP") (pinfunction "TP_TP") (pintype "input"))
      (node (ref "TP33") (pin "TP") (pinfunction "TP_TP") (pintype "input"))
      (node (ref "TP34") (pin "TP") (pinfunction "TP_TP") (pintype "input"))
      (node (ref "TP35") (pin "TP") (pinfunction "TP_TP") (pintype "input"))
      (node (ref "TP36") (pin "TP") (pinfunction "TP_TP") (pintype "input"))
      (node (ref "TP37") (pin "TP") (pinfunction "TP_TP") (pintype "input"))
      (node (ref "TP38") (pin "TP") (pinfunction "TP_TP") (pintype "input"))
      (node (ref "U$10") (pin "P$2") (pinfunction "2_P$2") (pintype "bidirectional"))
      (node (ref "U$11") (pin "P$2") (pinfunction "2_P$2") (pintype "bidirectional"))
      (node (ref "U$12") (pin "P$2") (pinfunction "2_P$2") (pintype "bidirectional"))
      (node (ref "U$13") (pin "P$2") (pinfunction "2_P$2") (pintype "bidirectional"))
      (node (ref "U$14") (pin "P$2") (pinfunction "2_P$2") (pintype "bidirectional"))
      (node (ref "U$16") (pin "P$2") (pinfunction "2_P$2") (pintype "bidirectional"))
      (node (ref "U$17") (pin "2") (pinfunction "GND_2") (pintype "power_in"))
      (node (ref "U$3") (pin "1") (pinfunction "GND_1") (pintype "power_in"))
      (node (ref "U$4") (pin "P$2") (pinfunction "2_P$2") (pintype "bidirectional"))
      (node (ref "U$9") (pin "P$2") (pinfunction "2_P$2") (pintype "bidirectional"))
      (node (ref "U1") (pin "GND") (pinfunction "GND_GND") (pintype "bidirectional"))
    )
    (net (code "35") (name "/HORISONTAL") (class "Default")
      (node (ref "J5") (pin "5") (pinfunction "5_5") (pintype "passive"))
      (node (ref "U$1") (pin "P$36") (pinfunction "PA0_P$36") (pintype "bidirectional"))
    )
    (net (code "36") (name "/HORISONTAL2_S") (class "Default")
      (node (ref "S2") (pin "H2") (pinfunction "H_H2") (pintype "bidirectional"))
      (node (ref "U$17") (pin "10") (pinfunction "A3_10") (pintype "input"))
    )
    (net (code "37") (name "/HORISONTAL_S") (class "Default")
      (node (ref "J7") (pin "5") (pinfunction "5_5") (pintype "passive"))
      (node (ref "S1") (pin "H2") (pinfunction "H_H2") (pintype "bidirectional"))
    )
    (net (code "38") (name "/MISO") (class "Default")
      (node (ref "M1") (pin "7") (pinfunction "MISO_7") (pintype "bidirectional"))
      (node (ref "U$1") (pin "P$30") (pinfunction "PA6_P$30") (pintype "bidirectional"))
    )
    (net (code "39") (name "/MOS") (class "Default")
      (node (ref "U$1") (pin "P$17") (pinfunction "PB9_P$17") (pintype "bidirectional"))
    )
    (net (code "40") (name "/MOSI") (class "Default")
      (node (ref "M1") (pin "6") (pinfunction "MOSI_6") (pintype "bidirectional"))
      (node (ref "U$1") (pin "P$29") (pinfunction "PA7_P$29") (pintype "bidirectional"))
    )
    (net (code "41") (name "/ON") (class "Default")
      (node (ref "D1") (pin "A") (pinfunction "A_A") (pintype "passive"))
      (node (ref "U$1") (pin "P$13") (pinfunction "PB5_P$13") (pintype "bidirectional"))
    )
    (net (code "42") (name "/RX") (class "Default")
      (node (ref "U$1") (pin "P$7") (pinfunction "PA10_P$7") (pintype "bidirectional"))
      (node (ref "U$6") (pin "JP2.1") (pinfunction "TX_JP2.1") (pintype "bidirectional"))
    )
    (net (code "43") (name "/SCK") (class "Default")
      (node (ref "M1") (pin "5") (pinfunction "SCK_5") (pintype "bidirectional"))
      (node (ref "U$1") (pin "P$31") (pinfunction "PA5_P$31") (pintype "bidirectional"))
    )
    (net (code "44") (name "/SCL") (class "Default")
      (node (ref "J4") (pin "6") (pinfunction "6_6") (pintype "passive"))
      (node (ref "U$1") (pin "P$15") (pinfunction "PB7_P$15") (pintype "bidirectional"))
    )
    (net (code "45") (name "/SCL_IMU") (class "Default")
      (node (ref "J5") (pin "15") (pinfunction "15_15") (pintype "passive"))
      (node (ref "U$1") (pin "P$26") (pinfunction "PB10_P$26") (pintype "bidirectional"))
    )
    (net (code "46") (name "/SCL_IMU_S") (class "Default")
      (node (ref "J7") (pin "15") (pinfunction "15_15") (pintype "passive"))
      (node (ref "R7") (pin "1") (pinfunction "1_1") (pintype "passive"))
      (node (ref "U$17") (pin "3") (pinfunction "SCL_3") (pintype "bidirectional"))
    )
    (net (code "47") (name "/SCL_S") (class "Default")
      (node (ref "J6") (pin "6") (pinfunction "6_6") (pintype "passive"))
      (node (ref "R8") (pin "1") (pinfunction "1_1") (pintype "passive"))
      (node (ref "U$3") (pin "3") (pinfunction "SCL_3") (pintype "bidirectional"))
      (node (ref "U1") (pin "SCL") (pinfunction "SCL_SCL") (pintype "bidirectional"))
    )
    (net (code "48") (name "/SDA") (class "Default")
      (node (ref "J4") (pin "7") (pinfunction "7_7") (pintype "passive"))
      (node (ref "U$1") (pin "P$14") (pinfunction "PB6_P$14") (pintype "bidirectional"))
    )
    (net (code "49") (name "/SDA_IMU") (class "Default")
      (node (ref "J5") (pin "16") (pinfunction "16_16") (pintype "passive"))
      (node (ref "U$1") (pin "P$25") (pinfunction "PB11_P$25") (pintype "bidirectional"))
    )
    (net (code "50") (name "/SDA_IMU_S") (class "Default")
      (node (ref "J7") (pin "16") (pinfunction "16_16") (pintype "passive"))
      (node (ref "R6") (pin "1") (pinfunction "1_1") (pintype "passive"))
      (node (ref "U$17") (pin "4") (pinfunction "SDA_4") (pintype "bidirectional"))
    )
    (net (code "51") (name "/SDA_S") (class "Default")
      (node (ref "J6") (pin "7") (pinfunction "7_7") (pintype "passive"))
      (node (ref "R9") (pin "1") (pinfunction "1_1") (pintype "passive"))
      (node (ref "U$3") (pin "4") (pinfunction "SDA_4") (pintype "bidirectional"))
      (node (ref "U1") (pin "SDA") (pinfunction "SDA_SDA") (pintype "bidirectional"))
    )
    (net (code "52") (name "/SELECT2_S") (class "Default")
      (node (ref "C10") (pin "1") (pinfunction "1_1") (pintype "passive"))
      (node (ref "R25") (pin "1") (pinfunction "1_1") (pintype "passive"))
      (node (ref "U$17") (pin "8") (pinfunction "A1_8") (pintype "input"))
    )
    (net (code "53") (name "/TX") (class "Default")
      (node (ref "U$1") (pin "P$6") (pinfunction "PA9_P$6") (pintype "bidirectional"))
      (node (ref "U$6") (pin "JP2.2") (pinfunction "RX_JP2.2") (pintype "bidirectional"))
    )
    (net (code "54") (name "/VERTICAL") (class "Default")
      (node (ref "J5") (pin "6") (pinfunction "6_6") (pintype "passive"))
      (node (ref "U$1") (pin "P$35") (pinfunction "PA1_P$35") (pintype "bidirectional"))
    )
    (net (code "55") (name "/VERTICAL2_S") (class "Default")
      (node (ref "S2") (pin "V2") (pinfunction "V_V2") (pintype "bidirectional"))
      (node (ref "U$17") (pin "9") (pinfunction "A2_9") (pintype "input"))
    )
    (net (code "56") (name "/VERTICAL_S") (class "Default")
      (node (ref "J7") (pin "6") (pinfunction "6_6") (pintype "passive"))
      (node (ref "S1") (pin "V2") (pinfunction "V_V2") (pintype "bidirectional"))
    )
    (net (code "57") (name "/VIN") (class "Default")
      (node (ref "J1") (pin "1") (pinfunction "1_1") (pintype "passive"))
      (node (ref "K6") (pin "11") (pinfunction "O_11") (pintype "passive"))
      (node (ref "R13") (pin "2") (pinfunction "2_2") (pintype "passive"))
      (node (ref "U$18") (pin "IN+") (pinfunction "IN+_IN+") (pintype "bidirectional"))
    )
    (net (code "58") (name "/VIN_PIN") (class "Default")
      (node (ref "D5") (pin "A") (pinfunction "A_A") (pintype "passive"))
      (node (ref "R13") (pin "1") (pinfunction "1_1") (pintype "passive"))
      (node (ref "U$1") (pin "P$12") (pinfunction "PB4_P$12") (pintype "bidirectional"))
    )
    (net (code "59") (name "GND") (class "Default")
      (node (ref "BAT") (pin "2") (pinfunction "2_2") (pintype "passive"))
      (node (ref "BUZZER") (pin "1") (pinfunction "1_1") (pintype "passive"))
      (node (ref "J4") (pin "2") (pinfunction "2_2") (pintype "passive"))
      (node (ref "J5") (pin "19") (pinfunction "19_19") (pintype "passive"))
      (node (ref "J5") (pin "20") (pinfunction "20_20") (pintype "passive"))
      (node (ref "K6") (pin "16") (pinfunction "2_16") (pintype "passive"))
      (node (ref "M1") (pin "1") (pinfunction "GND_1") (pintype "power_in"))
      (node (ref "MOTOR") (pin "1") (pinfunction "1_1") (pintype "passive"))
      (node (ref "R10") (pin "2") (pinfunction "2_2") (pintype "passive"))
      (node (ref "R3") (pin "1") (pinfunction "1_1") (pintype "passive"))
      (node (ref "R4") (pin "1") (pinfunction "1_1") (pintype "passive"))
      (node (ref "TP1") (pin "TP") (pinfunction "TP_TP") (pintype "input"))
      (node (ref "TP10") (pin "TP") (pinfunction "TP_TP") (pintype "input"))
      (node (ref "TP11") (pin "TP") (pinfunction "TP_TP") (pintype "input"))
      (node (ref "TP12") (pin "TP") (pinfunction "TP_TP") (pintype "input"))
      (node (ref "TP13") (pin "TP") (pinfunction "TP_TP") (pintype "input"))
      (node (ref "TP14") (pin "TP") (pinfunction "TP_TP") (pintype "input"))
      (node (ref "TP15") (pin "TP") (pinfunction "TP_TP") (pintype "input"))
      (node (ref "TP16") (pin "TP") (pinfunction "TP_TP") (pintype "input"))
      (node (ref "TP18") (pin "TP") (pinfunction "TP_TP") (pintype "input"))
      (node (ref "TP2") (pin "TP") (pinfunction "TP_TP") (pintype "input"))
      (node (ref "TP20") (pin "TP") (pinfunction "TP_TP") (pintype "input"))
      (node (ref "TP21") (pin "TP") (pinfunction "TP_TP") (pintype "input"))
      (node (ref "TP22") (pin "TP") (pinfunction "TP_TP") (pintype "input"))
      (node (ref "TP23") (pin "TP") (pinfunction "TP_TP") (pintype "input"))
      (node (ref "TP24") (pin "TP") (pinfunction "TP_TP") (pintype "input"))
      (node (ref "TP3") (pin "TP") (pinfunction "TP_TP") (pintype "input"))
      (node (ref "TP4") (pin "TP") (pinfunction "TP_TP") (pintype "input"))
      (node (ref "TP5") (pin "TP") (pinfunction "TP_TP") (pintype "input"))
      (node (ref "TP6") (pin "TP") (pinfunction "TP_TP") (pintype "input"))
      (node (ref "TP7") (pin "TP") (pinfunction "TP_TP") (pintype "input"))
      (node (ref "TP8") (pin "TP") (pinfunction "TP_TP") (pintype "input"))
      (node (ref "TP9") (pin "TP") (pinfunction "TP_TP") (pintype "input"))
      (node (ref "U$1") (pin "P$19") (pinfunction "GND2_P$19") (pintype "bidirectional"))
      (node (ref "U$1") (pin "P$21") (pinfunction "GND1_P$21") (pintype "power_in"))
      (node (ref "U$1") (pin "P$22") (pinfunction "GND_P$22") (pintype "bidirectional"))
      (node (ref "U$18") (pin "IN-") (pinfunction "IN-_IN-") (pintype "bidirectional"))
      (node (ref "U$18") (pin "OUT-") (pinfunction "OUT-_OUT-") (pintype "bidirectional"))
      (node (ref "U$2") (pin "4") (pinfunction "GND_4") (pintype "power_in"))
      (node (ref "U$5") (pin "BAT-") (pinfunction "BAT-_BAT-") (pintype "power_in"))
      (node (ref "U$6") (pin "JP2.7") (pinfunction "GND_JP2.7") (pintype "power_in"))
      (node (ref "U$7") (pin "IN-") (pinfunction "IN-_IN-") (pintype "bidirectional"))
      (node (ref "U$7") (pin "OUT-") (pinfunction "OUT-_OUT-") (pintype "bidirectional"))
    )
    (net (code "60") (name "Net-(BUZZER-Pad2)") (class "Default")
      (node (ref "BUZZER") (pin "2") (pinfunction "2_2") (pintype "passive"))
      (node (ref "R14") (pin "1") (pinfunction "1_1") (pintype "passive"))
    )
    (net (code "61") (name "Net-(D6-PadA)") (class "Default")
      (node (ref "D6") (pin "A") (pinfunction "A_A") (pintype "passive"))
      (node (ref "U$7") (pin "OUT+") (pinfunction "OUT+_OUT+") (pintype "bidirectional"))
    )
    (net (code "62") (name "Net-(S1-SEL+)") (class "Default")
      (node (ref "R22") (pin "1") (pinfunction "1_1") (pintype "passive"))
      (node (ref "R31") (pin "2") (pinfunction "2_2") (pintype "passive"))
      (node (ref "S1") (pin "B1A") (pinfunction "SEL+_B1A") (pintype "bidirectional"))
    )
    (net (code "63") (name "Net-(S2-SEL+)") (class "Default")
      (node (ref "R21") (pin "1") (pinfunction "1_1") (pintype "passive"))
      (node (ref "R25") (pin "2") (pinfunction "2_2") (pintype "passive"))
      (node (ref "S2") (pin "B1A") (pinfunction "SEL+_B1A") (pintype "bidirectional"))
    )
    (net (code "64") (name "Net-(U$4-1)") (class "Default")
      (node (ref "R19") (pin "2") (pinfunction "2_2") (pintype "passive"))
      (node (ref "R23") (pin "1") (pinfunction "1_1") (pintype "passive"))
      (node (ref "S4") (pin "1") (pinfunction "1_1") (pintype "passive"))
      (node (ref "U$4") (pin "P$1") (pinfunction "1_P$1") (pintype "bidirectional"))
    )
    (net (code "65") (name "Net-(U$8-1)") (class "Default")
      (node (ref "C1") (pin "2") (pinfunction "2_2") (pintype "passive"))
      (node (ref "D2") (pin "A") (pinfunction "A_A") (pintype "passive"))
      (node (ref "R5") (pin "1") (pinfunction "1_1") (pintype "passive"))
      (node (ref "U$8") (pin "P$1") (pinfunction "1_P$1") (pintype "bidirectional"))
    )
    (net (code "66") (name "Net-(U$9-1)") (class "Default")
      (node (ref "R11") (pin "2") (pinfunction "2_2") (pintype "passive"))
      (node (ref "R26") (pin "1") (pinfunction "1_1") (pintype "passive"))
      (node (ref "U$9") (pin "P$1") (pinfunction "1_P$1") (pintype "bidirectional"))
    )
    (net (code "67") (name "Net-(U$10-1)") (class "Default")
      (node (ref "R1") (pin "1") (pinfunction "1_1") (pintype "passive"))
      (node (ref "R20") (pin "2") (pinfunction "2_2") (pintype "passive"))
      (node (ref "S3") (pin "1") (pinfunction "1_1") (pintype "passive"))
      (node (ref "U$10") (pin "P$1") (pinfunction "1_P$1") (pintype "bidirectional"))
    )
    (net (code "68") (name "Net-(U$11-1)") (class "Default")
      (node (ref "R12") (pin "2") (pinfunction "2_2") (pintype "passive"))
      (node (ref "R24") (pin "1") (pinfunction "1_1") (pintype "passive"))
      (node (ref "S5") (pin "1") (pinfunction "1_1") (pintype "passive"))
      (node (ref "U$11") (pin "P$1") (pinfunction "1_P$1") (pintype "bidirectional"))
    )
    (net (code "69") (name "Net-(U$12-1)") (class "Default")
      (node (ref "R16") (pin "2") (pinfunction "2_2") (pintype "passive"))
      (node (ref "R28") (pin "1") (pinfunction "1_1") (pintype "passive"))
      (node (ref "U$12") (pin "P$1") (pinfunction "1_P$1") (pintype "bidirectional"))
    )
    (net (code "70") (name "Net-(U$13-1)") (class "Default")
      (node (ref "R15") (pin "2") (pinfunction "2_2") (pintype "passive"))
      (node (ref "R27") (pin "1") (pinfunction "1_1") (pintype "passive"))
      (node (ref "S7") (pin "1") (pinfunction "1_1") (pintype "passive"))
      (node (ref "U$13") (pin "P$1") (pinfunction "1_P$1") (pintype "bidirectional"))
    )
    (net (code "71") (name "Net-(U$14-1)") (class "Default")
      (node (ref "R17") (pin "2") (pinfunction "2_2") (pintype "passive"))
      (node (ref "R29") (pin "1") (pinfunction "1_1") (pintype "passive"))
      (node (ref "S9") (pin "1") (pinfunction "1_1") (pintype "passive"))
      (node (ref "U$14") (pin "P$1") (pinfunction "1_P$1") (pintype "bidirectional"))
    )
    (net (code "72") (name "Net-(U$16-1)") (class "Default")
      (node (ref "R18") (pin "2") (pinfunction "2_2") (pintype "passive"))
      (node (ref "R30") (pin "1") (pinfunction "1_1") (pintype "passive"))
      (node (ref "S10") (pin "1") (pinfunction "1_1") (pintype "passive"))
      (node (ref "U$16") (pin "P$1") (pinfunction "1_P$1") (pintype "bidirectional"))
    )
    (net (code "73") (name "unconnected-(J4-Pad4)") (class "Default")
      (node (ref "J4") (pin "4") (pinfunction "4_4") (pintype "passive"))
    )
    (net (code "74") (name "unconnected-(J4-Pad5)") (class "Default")
      (node (ref "J4") (pin "5") (pinfunction "5_5") (pintype "passive"))
    )
    (net (code "75") (name "unconnected-(J4-Pad8)") (class "Default")
      (node (ref "J4") (pin "8") (pinfunction "8_8") (pintype "passive"))
    )
    (net (code "76") (name "unconnected-(J4-Pad9)") (class "Default")
      (node (ref "J4") (pin "9") (pinfunction "9_9") (pintype "passive"))
    )
    (net (code "77") (name "unconnected-(J4-Pad12)") (class "Default")
      (node (ref "J4") (pin "12") (pinfunction "12_12") (pintype "passive"))
    )
    (net (code "78") (name "unconnected-(J4-Pad13)") (class "Default")
      (node (ref "J4") (pin "13") (pinfunction "13_13") (pintype "passive"))
    )
    (net (code "79") (name "unconnected-(J4-Pad14)") (class "Default")
      (node (ref "J4") (pin "14") (pinfunction "14_14") (pintype "passive"))
    )
    (net (code "80") (name "unconnected-(J4-Pad15)") (class "Default")
      (node (ref "J4") (pin "15") (pinfunction "15_15") (pintype "passive"))
    )
    (net (code "81") (name "unconnected-(J5-Pad1)") (class "Default")
      (node (ref "J5") (pin "1") (pinfunction "1_1") (pintype "passive"))
    )
    (net (code "82") (name "unconnected-(J5-Pad2)") (class "Default")
      (node (ref "J5") (pin "2") (pinfunction "2_2") (pintype "passive"))
    )
    (net (code "83") (name "unconnected-(J5-Pad3)") (class "Default")
      (node (ref "J5") (pin "3") (pinfunction "3_3") (pintype "passive"))
    )
    (net (code "84") (name "unconnected-(J5-Pad4)") (class "Default")
      (node (ref "J5") (pin "4") (pinfunction "4_4") (pintype "passive"))
    )
    (net (code "85") (name "unconnected-(J5-Pad7)") (class "Default")
      (node (ref "J5") (pin "7") (pinfunction "7_7") (pintype "passive"))
    )
    (net (code "86") (name "unconnected-(J5-Pad8)") (class "Default")
      (node (ref "J5") (pin "8") (pinfunction "8_8") (pintype "passive"))
    )
    (net (code "87") (name "unconnected-(J5-Pad9)") (class "Default")
      (node (ref "J5") (pin "9") (pinfunction "9_9") (pintype "passive"))
    )
    (net (code "88") (name "unconnected-(J5-Pad10)") (class "Default")
      (node (ref "J5") (pin "10") (pinfunction "10_10") (pintype "passive"))
    )
    (net (code "89") (name "unconnected-(J5-Pad11)") (class "Default")
      (node (ref "J5") (pin "11") (pinfunction "11_11") (pintype "passive"))
    )
    (net (code "90") (name "unconnected-(J5-Pad12)") (class "Default")
      (node (ref "J5") (pin "12") (pinfunction "12_12") (pintype "passive"))
    )
    (net (code "91") (name "unconnected-(J5-Pad17)") (class "Default")
      (node (ref "J5") (pin "17") (pinfunction "17_17") (pintype "passive"))
    )
    (net (code "92") (name "unconnected-(J6-Pad4)") (class "Default")
      (node (ref "J6") (pin "4") (pinfunction "4_4") (pintype "passive"))
    )
    (net (code "93") (name "unconnected-(J6-Pad5)") (class "Default")
      (node (ref "J6") (pin "5") (pinfunction "5_5") (pintype "passive"))
    )
    (net (code "94") (name "unconnected-(J6-Pad8)") (class "Default")
      (node (ref "J6") (pin "8") (pinfunction "8_8") (pintype "passive"))
    )
    (net (code "95") (name "unconnected-(J6-Pad9)") (class "Default")
      (node (ref "J6") (pin "9") (pinfunction "9_9") (pintype "passive"))
    )
    (net (code "96") (name "unconnected-(J6-Pad12)") (class "Default")
      (node (ref "J6") (pin "12") (pinfunction "12_12") (pintype "passive"))
    )
    (net (code "97") (name "unconnected-(J6-Pad13)") (class "Default")
      (node (ref "J6") (pin "13") (pinfunction "13_13") (pintype "passive"))
    )
    (net (code "98") (name "unconnected-(J6-Pad14)") (class "Default")
      (node (ref "J6") (pin "14") (pinfunction "14_14") (pintype "passive"))
    )
    (net (code "99") (name "unconnected-(J6-Pad15)") (class "Default")
      (node (ref "J6") (pin "15") (pinfunction "15_15") (pintype "passive"))
    )
    (net (code "100") (name "unconnected-(J7-Pad1)") (class "Default")
      (node (ref "J7") (pin "1") (pinfunction "1_1") (pintype "passive"))
    )
    (net (code "101") (name "unconnected-(J7-Pad2)") (class "Default")
      (node (ref "J7") (pin "2") (pinfunction "2_2") (pintype "passive"))
    )
    (net (code "102") (name "unconnected-(J7-Pad3)") (class "Default")
      (node (ref "J7") (pin "3") (pinfunction "3_3") (pintype "passive"))
    )
    (net (code "103") (name "unconnected-(J7-Pad4)") (class "Default")
      (node (ref "J7") (pin "4") (pinfunction "4_4") (pintype "passive"))
    )
    (net (code "104") (name "unconnected-(J7-Pad7)") (class "Default")
      (node (ref "J7") (pin "7") (pinfunction "7_7") (pintype "passive"))
    )
    (net (code "105") (name "unconnected-(J7-Pad8)") (class "Default")
      (node (ref "J7") (pin "8") (pinfunction "8_8") (pintype "passive"))
    )
    (net (code "106") (name "unconnected-(J7-Pad9)") (class "Default")
      (node (ref "J7") (pin "9") (pinfunction "9_9") (pintype "passive"))
    )
    (net (code "107") (name "unconnected-(J7-Pad10)") (class "Default")
      (node (ref "J7") (pin "10") (pinfunction "10_10") (pintype "passive"))
    )
    (net (code "108") (name "unconnected-(J7-Pad11)") (class "Default")
      (node (ref "J7") (pin "11") (pinfunction "11_11") (pintype "passive"))
    )
    (net (code "109") (name "unconnected-(J7-Pad12)") (class "Default")
      (node (ref "J7") (pin "12") (pinfunction "12_12") (pintype "passive"))
    )
    (net (code "110") (name "unconnected-(J7-Pad17)") (class "Default")
      (node (ref "J7") (pin "17") (pinfunction "17_17") (pintype "passive"))
    )
    (net (code "111") (name "unconnected-(K6-Pad1)") (class "Default")
      (node (ref "K6") (pin "1") (pinfunction "1_1") (pintype "passive"))
    )
    (net (code "112") (name "unconnected-(M1-IRQ-Pad8)") (class "Default")
      (node (ref "M1") (pin "8") (pinfunction "IRQ_8") (pintype "bidirectional"))
    )
    (net (code "113") (name "unconnected-(MOTOR-Pad2)") (class "Default")
      (node (ref "MOTOR") (pin "2") (pinfunction "2_2") (pintype "passive"))
    )
    (net (code "114") (name "unconnected-(U$1-PA11-PadP$8)") (class "Default")
      (node (ref "U$1") (pin "P$8") (pinfunction "PA11_P$8") (pintype "bidirectional"))
    )
    (net (code "115") (name "unconnected-(U$1-PA12-PadP$9)") (class "Default")
      (node (ref "U$1") (pin "P$9") (pinfunction "PA12_P$9") (pintype "bidirectional"))
    )
    (net (code "116") (name "unconnected-(U$1-PC13-PadP$39)") (class "Default")
      (node (ref "U$1") (pin "P$39") (pinfunction "PC13_P$39") (pintype "bidirectional"))
    )
    (net (code "117") (name "unconnected-(U$1-RESET-PadP$24)") (class "Default")
      (node (ref "U$1") (pin "P$24") (pinfunction "RESET_P$24") (pintype "bidirectional"))
    )
    (net (code "118") (name "unconnected-(U$1-VBAT-PadP$40)") (class "Default")
      (node (ref "U$1") (pin "P$40") (pinfunction "VBAT_P$40") (pintype "bidirectional"))
    )
    (net (code "119") (name "unconnected-(U$2-EN-Pad6)") (class "Default")
      (node (ref "U$2") (pin "6") (pinfunction "EN_6") (pintype "bidirectional"))
    )
    (net (code "120") (name "unconnected-(U$2-STATE-Pad1)") (class "Default")
      (node (ref "U$2") (pin "1") (pinfunction "STATE_1") (pintype "bidirectional"))
    )
    (net (code "121") (name "unconnected-(U$6-A0-PadJP1.2)") (class "Default")
      (node (ref "U$6") (pin "JP1.2") (pinfunction "A0_JP1.2") (pintype "bidirectional"))
    )
    (net (code "122") (name "unconnected-(U$6-D0-PadJP1.3)") (class "Default")
      (node (ref "U$6") (pin "JP1.3") (pinfunction "D0_JP1.3") (pintype "bidirectional"))
    )
    (net (code "123") (name "unconnected-(U$6-D1-PadJP2.3)") (class "Default")
      (node (ref "U$6") (pin "JP2.3") (pinfunction "D1_JP2.3") (pintype "bidirectional"))
    )
    (net (code "124") (name "unconnected-(U$6-D2-PadJP2.4)") (class "Default")
      (node (ref "U$6") (pin "JP2.4") (pinfunction "D2_JP2.4") (pintype "bidirectional"))
    )
    (net (code "125") (name "unconnected-(U$6-D3-PadJP2.5)") (class "Default")
      (node (ref "U$6") (pin "JP2.5") (pinfunction "D3_JP2.5") (pintype "bidirectional"))
    )
    (net (code "126") (name "unconnected-(U$6-D4-PadJP2.6)") (class "Default")
      (node (ref "U$6") (pin "JP2.6") (pinfunction "D4_JP2.6") (pintype "bidirectional"))
    )
    (net (code "127") (name "unconnected-(U$6-D5-PadJP1.4)") (class "Default")
      (node (ref "U$6") (pin "JP1.4") (pinfunction "D5_JP1.4") (pintype "bidirectional"))
    )
    (net (code "128") (name "unconnected-(U$6-D6-PadJP1.5)") (class "Default")
      (node (ref "U$6") (pin "JP1.5") (pinfunction "D6_JP1.5") (pintype "bidirectional"))
    )
    (net (code "129") (name "unconnected-(U$6-D7-PadJP1.6)") (class "Default")
      (node (ref "U$6") (pin "JP1.6") (pinfunction "D7_JP1.6") (pintype "bidirectional"))
    )
    (net (code "130") (name "unconnected-(U$6-D8-PadJP1.7)") (class "Default")
      (node (ref "U$6") (pin "JP1.7") (pinfunction "D8_JP1.7") (pintype "bidirectional"))
    )
    (net (code "131") (name "unconnected-(U$6-RST-PadJP1.1)") (class "Default")
      (node (ref "U$6") (pin "JP1.1") (pinfunction "RST_JP1.1") (pintype "bidirectional"))
    )
    (net (code "132") (name "unconnected-(U$17-A0-Pad7)") (class "Default")
      (node (ref "U$17") (pin "7") (pinfunction "A0_7") (pintype "input"))
    )
    (net (code "133") (name "unconnected-(U$17-ADDR-Pad5)") (class "Default")
      (node (ref "U$17") (pin "5") (pinfunction "ADDR_5") (pintype "bidirectional"))
    )
    (net (code "134") (name "unconnected-(U$17-ALRT-Pad6)") (class "Default")
      (node (ref "U$17") (pin "6") (pinfunction "ALRT_6") (pintype "bidirectional"))
    )
    (net (code "135") (name "unconnected-(U$18-PadB+)") (class "Default")
      (node (ref "U$18") (pin "B+") (pinfunction "B+_B+") (pintype "bidirectional"))
    )
    (net (code "136") (name "unconnected-(U$18-PadB-)") (class "Default")
      (node (ref "U$18") (pin "B-") (pinfunction "B-_B-") (pintype "bidirectional"))
    )
    (net (code "137") (name "unconnected-(U1-PadADO)") (class "Default")
      (node (ref "U1") (pin "ADO") (pinfunction "ADO_ADO") (pintype "bidirectional"))
    )
    (net (code "138") (name "unconnected-(U1-PadINT)") (class "Default")
      (node (ref "U1") (pin "INT") (pinfunction "INT_INT") (pintype "bidirectional"))
    )
    (net (code "139") (name "unconnected-(U1-PadXCL)") (class "Default")
      (node (ref "U1") (pin "XCL") (pinfunction "XCL_XCL") (pintype "bidirectional"))
    )
    (net (code "140") (name "unconnected-(U1-PadXDA)") (class "Default")
      (node (ref "U1") (pin "XDA") (pinfunction "XDA_XDA") (pintype "bidirectional"))
    )
  )
)
